# release.net
KiCad netlist of a schematic drawn in EAGLE
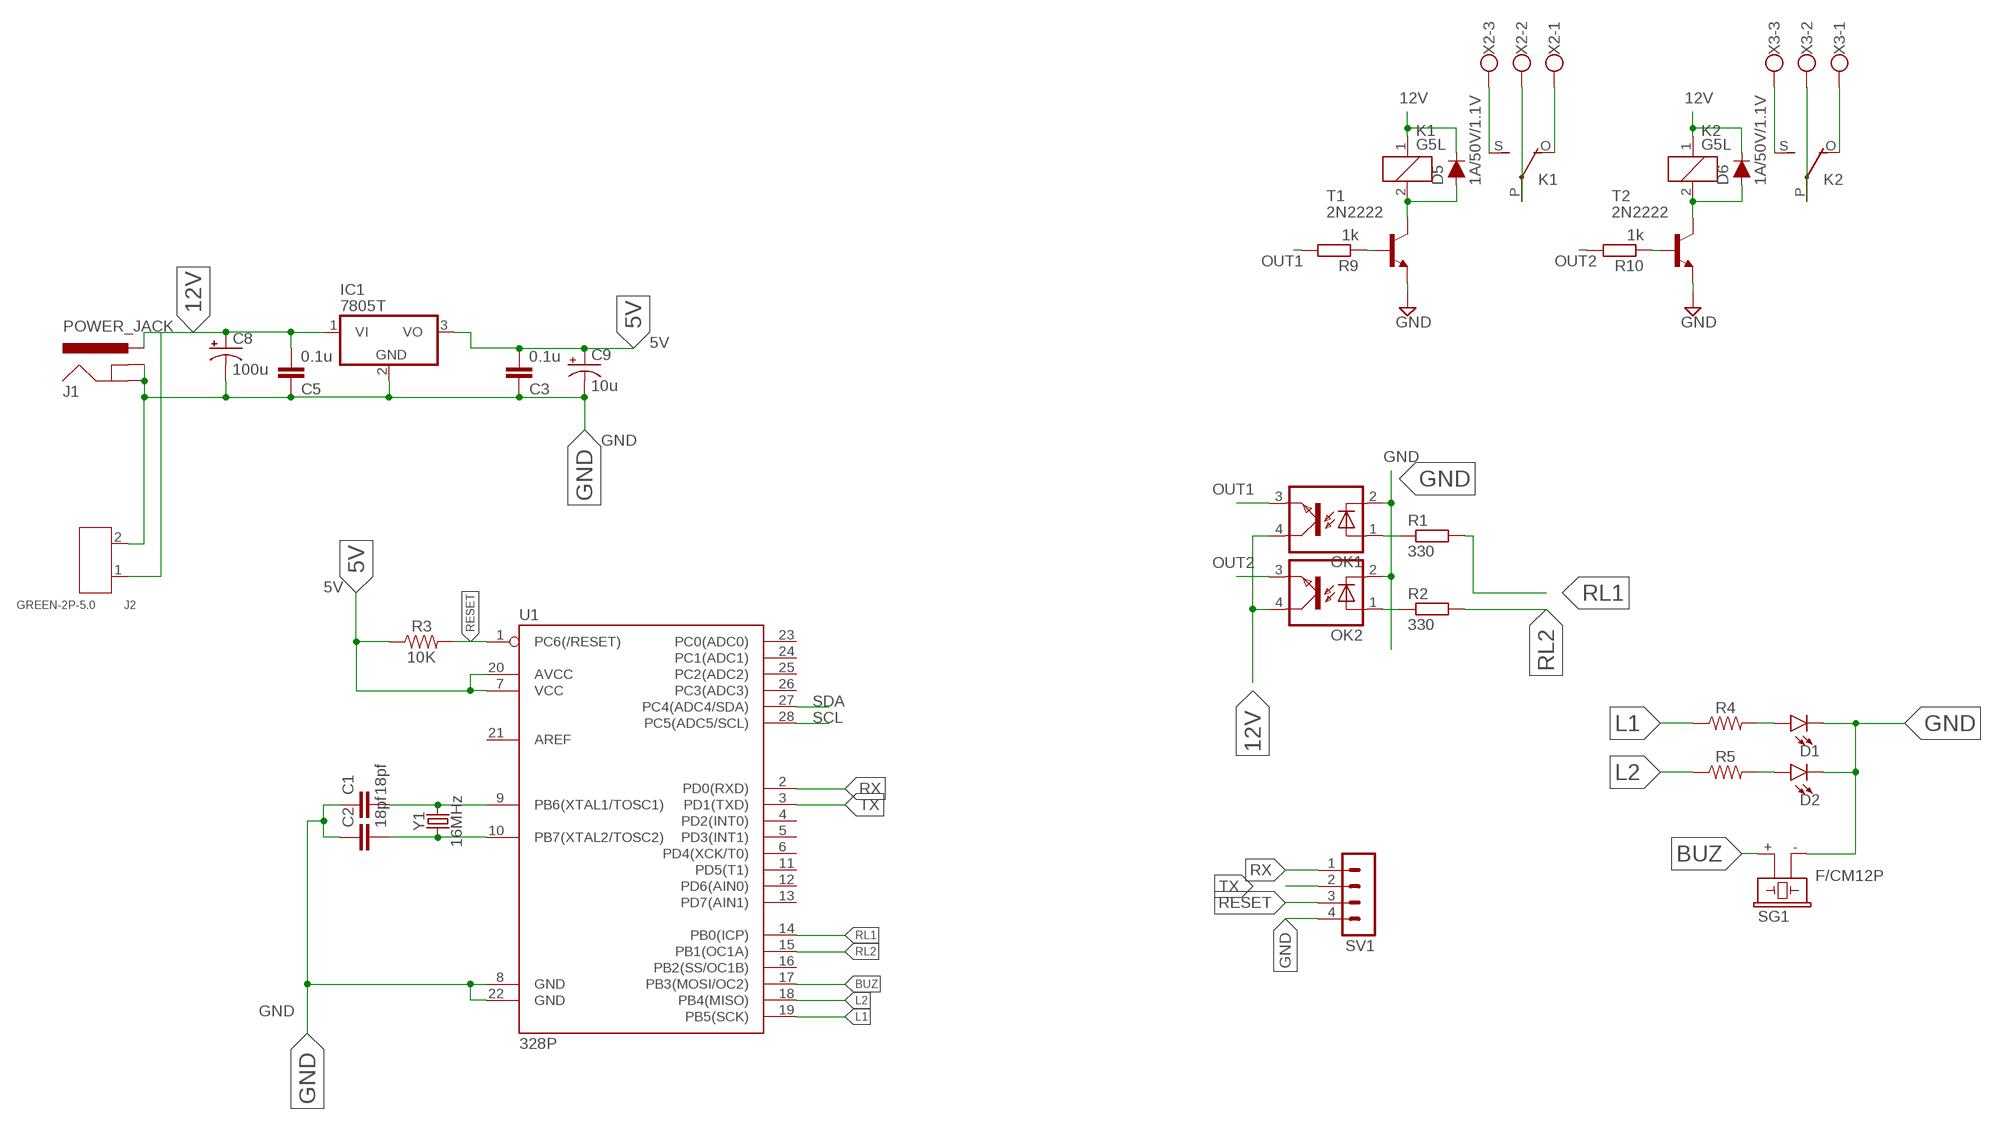
[diagram p0: schematic, sheet 1]

(export (version "E")
  (design (tool "Eeschema 10.0.6"))
  (components
    (comp (ref "C1")
      (value "18pf")
      (footprint "eagle-import:C2.5-3")
      (libsource (lib "eagle-import") (part "C2,5-3"))
    )
    (comp (ref "C2")
      (value "18pf")
      (footprint "eagle-import:C2.5-3")
      (libsource (lib "eagle-import") (part "C2,5-3"))
    )
    (comp (ref "C3")
      (value "0.1u")
      (footprint "eagle-import:C2.5-3")
      (libsource (lib "eagle-import") (part "C2,5-3"))
    )
    (comp (ref "C5")
      (value "0.1u")
      (footprint "eagle-import:C2.5-3")
      (libsource (lib "eagle-import") (part "C2,5-3"))
    )
    (comp (ref "C8")
      (value "100u")
      (footprint "eagle-import:E2,5-7")
      (libsource (lib "eagle-import") (part "CPOL-USE2.5-7"))
    )
    (comp (ref "C9")
      (value "10u")
      (footprint "eagle-import:E2,5-5")
      (libsource (lib "eagle-import") (part "CPOL-USE2.5-5"))
    )
    (comp (ref "D1")
      (value "LED5MM")
      (footprint "eagle-import:LED_5MM")
      (libsource (lib "eagle-import") (part "LED5MM"))
    )
    (comp (ref "D2")
      (value "LED5MM")
      (footprint "eagle-import:LED_5MM")
      (libsource (lib "eagle-import") (part "LED5MM"))
    )
    (comp (ref "D5")
      (value "1A/50V/1.1V")
      (footprint "eagle-import:DIODE-1N4001")
      (libsource (lib "eagle-import") (part "DIODE-PTH"))
    )
    (comp (ref "D6")
      (value "1A/50V/1.1V")
      (footprint "eagle-import:DIODE-1N4001")
      (libsource (lib "eagle-import") (part "DIODE-PTH"))
    )
    (comp (ref "IC1")
      (value "7805T")
      (footprint "eagle-import:TO220H")
      (libsource (lib "eagle-import") (part "78T05"))
    )
    (comp (ref "J1")
      (value "POWER_JACK")
      (footprint "eagle-import:POWER_JACK_PTH")
      (libsource (lib "eagle-import") (part "POWER_JACK"))
    )
    (comp (ref "J2")
      (value "GREEN-2P-5.0")
      (footprint "eagle-import:H2-5.0-10.5X8.0MM")
      (libsource (lib "eagle-import") (part "SCREW-TERMINAL-GREEN(2P-5.0)"))
    )
    (comp (ref "K1")
      (value "G5L")
      (footprint "eagle-import:G5LE")
      (libsource (lib "eagle-import") (part "G5L"))
    )
    (comp (ref "K2")
      (value "G5L")
      (footprint "eagle-import:G5LE")
      (libsource (lib "eagle-import") (part "G5L"))
    )
    (comp (ref "OK1")
      (value "LTV816")
      (footprint "eagle-import:DIL04")
      (libsource (lib "eagle-import") (part "LTV816"))
    )
    (comp (ref "OK2")
      (value "LTV816")
      (footprint "eagle-import:DIL04")
      (libsource (lib "eagle-import") (part "LTV816"))
    )
    (comp (ref "R1")
      (value "330")
      (footprint "eagle-import:0207_7")
      (libsource (lib "eagle-import") (part "R-EU_0207/7"))
    )
    (comp (ref "R2")
      (value "330")
      (footprint "eagle-import:0207_7")
      (libsource (lib "eagle-import") (part "R-EU_0207/7"))
    )
    (comp (ref "R3")
      (value "10K")
      (footprint "eagle-import:AXIAL-0.3")
      (libsource (lib "eagle-import") (part "1KOHM-HORIZ-1/4W-5%"))
    )
    (comp (ref "R4")
      (value "RESISTORAXIAL-0.3")
      (footprint "eagle-import:AXIAL-0.3")
      (libsource (lib "eagle-import") (part "RESISTORAXIAL-0.3"))
    )
    (comp (ref "R5")
      (value "RESISTORAXIAL-0.3")
      (footprint "eagle-import:AXIAL-0.3")
      (libsource (lib "eagle-import") (part "RESISTORAXIAL-0.3"))
    )
    (comp (ref "R9")
      (value "1k")
      (footprint "eagle-import:0207_7")
      (libsource (lib "eagle-import") (part "resistor_348_R-EU_0207/7"))
    )
    (comp (ref "R10")
      (value "1k")
      (footprint "eagle-import:0207_7")
      (libsource (lib "eagle-import") (part "resistor_348_R-EU_0207/7"))
    )
    (comp (ref "SG1")
      (value "F/CM12P")
      (footprint "eagle-import:F_CM12P")
      (libsource (lib "eagle-import") (part "F/CM12P"))
    )
    (comp (ref "SV1")
      (value "MA04-1")
      (footprint "eagle-import:MA04-1")
      (libsource (lib "eagle-import") (part "MA04-1"))
    )
    (comp (ref "T1")
      (value "2N2222")
      (footprint "eagle-import:TO92-EBC-OVAL")
      (libsource (lib "eagle-import") (part "2N2222"))
    )
    (comp (ref "T2")
      (value "2N2222")
      (footprint "eagle-import:TO92-EBC-OVAL")
      (libsource (lib "eagle-import") (part "2N2222"))
    )
    (comp (ref "U1")
      (value "328P")
      (footprint "eagle-import:DIP28")
      (libsource (lib "eagle-import") (part "ATMEGA328P_PDIP"))
    )
    (comp (ref "X2")
      (value "W237-103")
      (footprint "eagle-import:W237-103")
      (fields (field (name "MPN") "237-103"))
      (libsource (lib "eagle-import") (part "W237-103"))
    )
    (comp (ref "X3")
      (value "W237-103")
      (footprint "eagle-import:W237-103")
      (fields (field (name "MPN") "237-103"))
      (libsource (lib "eagle-import") (part "W237-103"))
    )
    (comp (ref "Y1")
      (value "16MHz")
      (footprint "eagle-import:HC49US")
      (libsource (lib "eagle-import") (part "CRYSTAL-16MHZPTH-HC49US"))
    )
  )
  (nets
    (net (code "1") (name "/OUT1") (class "Default")
      (node (ref "OK1") (pin "3") (pinfunction "EMIT_3") (pintype "passive"))
      (node (ref "R9") (pin "2") (pinfunction "2_2") (pintype "passive"))
    )
    (net (code "2") (name "/OUT2") (class "Default")
      (node (ref "OK2") (pin "3") (pinfunction "EMIT_3") (pintype "passive"))
      (node (ref "R10") (pin "2") (pinfunction "2_2") (pintype "passive"))
    )
    (net (code "3") (name "/SCL") (class "Default")
      (node (ref "U1") (pin "28") (pinfunction "PC5(ADC5/SCL)_28") (pintype "bidirectional"))
    )
    (net (code "4") (name "/SDA") (class "Default")
      (node (ref "U1") (pin "27") (pinfunction "PC4(ADC4/SDA)_27") (pintype "bidirectional"))
    )
    (net (code "5") (name "5V") (class "Default")
      (node (ref "C3") (pin "2") (pinfunction "2_2") (pintype "passive"))
      (node (ref "C9") (pin "+") (pinfunction "+_+") (pintype "passive"))
      (node (ref "IC1") (pin "3") (pinfunction "VO_3") (pintype "passive"))
      (node (ref "R3") (pin "P$1") (pinfunction "1_P$1") (pintype "passive"))
      (node (ref "U1") (pin "20") (pinfunction "AVCC_20") (pintype "bidirectional"))
      (node (ref "U1") (pin "7") (pinfunction "VCC_7") (pintype "bidirectional"))
    )
    (net (code "6") (name "12V") (class "Default")
      (node (ref "C5") (pin "2") (pinfunction "2_2") (pintype "passive"))
      (node (ref "C8") (pin "+") (pinfunction "+_+") (pintype "passive"))
      (node (ref "D5") (pin "C") (pinfunction "C_C") (pintype "passive"))
      (node (ref "D6") (pin "C") (pinfunction "C_C") (pintype "passive"))
      (node (ref "IC1") (pin "1") (pinfunction "VI_1") (pintype "input"))
      (node (ref "J1") (pin "PWR") (pinfunction "PWR_PWR") (pintype "bidirectional"))
      (node (ref "J2") (pin "1") (pinfunction "1_1") (pintype "bidirectional"))
      (node (ref "K1") (pin "1") (pinfunction "1_1") (pintype "passive"))
      (node (ref "K2") (pin "1") (pinfunction "1_1") (pintype "passive"))
      (node (ref "OK1") (pin "4") (pinfunction "COL_4") (pintype "passive"))
      (node (ref "OK2") (pin "4") (pinfunction "COL_4") (pintype "passive"))
    )
    (net (code "7") (name "BUZ") (class "Default")
      (node (ref "SG1") (pin "+") (pinfunction "1_+") (pintype "passive"))
      (node (ref "U1") (pin "17") (pinfunction "PB3(MOSI/OC2)_17") (pintype "bidirectional"))
    )
    (net (code "8") (name "GND") (class "Default")
      (node (ref "C1") (pin "1") (pinfunction "1_1") (pintype "passive"))
      (node (ref "C2") (pin "1") (pinfunction "1_1") (pintype "passive"))
      (node (ref "C3") (pin "1") (pinfunction "1_1") (pintype "passive"))
      (node (ref "C5") (pin "1") (pinfunction "1_1") (pintype "passive"))
      (node (ref "C8") (pin "-") (pinfunction "-_-") (pintype "passive"))
      (node (ref "C9") (pin "-") (pinfunction "-_-") (pintype "passive"))
      (node (ref "D1") (pin "K") (pinfunction "C_K") (pintype "passive"))
      (node (ref "D2") (pin "K") (pinfunction "C_K") (pintype "passive"))
      (node (ref "IC1") (pin "2") (pinfunction "GND_2") (pintype "passive"))
      (node (ref "J1") (pin "GND") (pinfunction "GND_GND") (pintype "bidirectional"))
      (node (ref "J1") (pin "GNDBREAK") (pinfunction "GNDBREAK_GNDBREAK") (pintype "bidirectional"))
      (node (ref "J2") (pin "2") (pinfunction "2_2") (pintype "bidirectional"))
      (node (ref "OK1") (pin "2") (pinfunction "C_2") (pintype "passive"))
      (node (ref "OK2") (pin "2") (pinfunction "C_2") (pintype "passive"))
      (node (ref "SG1") (pin "-") (pinfunction "2_-") (pintype "passive"))
      (node (ref "SV1") (pin "4") (pinfunction "4_4") (pintype "passive"))
      (node (ref "T1") (pin "E") (pinfunction "E_E") (pintype "passive"))
      (node (ref "T2") (pin "E") (pinfunction "E_E") (pintype "passive"))
      (node (ref "U1") (pin "22") (pinfunction "GND_22") (pintype "bidirectional"))
      (node (ref "U1") (pin "8") (pinfunction "GND_8") (pintype "bidirectional"))
    )
    (net (code "9") (name "L1") (class "Default")
      (node (ref "R4") (pin "P$1") (pinfunction "1_P$1") (pintype "passive"))
      (node (ref "U1") (pin "19") (pinfunction "PB5(SCK)_19") (pintype "bidirectional"))
    )
    (net (code "10") (name "L2") (class "Default")
      (node (ref "R5") (pin "P$1") (pinfunction "1_P$1") (pintype "passive"))
      (node (ref "U1") (pin "18") (pinfunction "PB4(MISO)_18") (pintype "bidirectional"))
    )
    (net (code "11") (name "Net-(D5-PadA)") (class "Default")
      (node (ref "D5") (pin "A") (pinfunction "A_A") (pintype "passive"))
      (node (ref "K1") (pin "2") (pinfunction "2_2") (pintype "passive"))
      (node (ref "T1") (pin "C") (pinfunction "C_C") (pintype "passive"))
    )
    (net (code "12") (name "Net-(D6-PadA)") (class "Default")
      (node (ref "D6") (pin "A") (pinfunction "A_A") (pintype "passive"))
      (node (ref "K2") (pin "2") (pinfunction "2_2") (pintype "passive"))
      (node (ref "T2") (pin "C") (pinfunction "C_C") (pintype "passive"))
    )
    (net (code "13") (name "Net-(OK1-A)") (class "Default")
      (node (ref "OK1") (pin "1") (pinfunction "A_1") (pintype "passive"))
      (node (ref "R1") (pin "1") (pinfunction "1_1") (pintype "passive"))
    )
    (net (code "14") (name "Net-(OK2-A)") (class "Default")
      (node (ref "OK2") (pin "1") (pinfunction "A_1") (pintype "passive"))
      (node (ref "R2") (pin "1") (pinfunction "1_1") (pintype "passive"))
    )
    (net (code "15") (name "Net-(R4-2)") (class "Default")
      (node (ref "D1") (pin "A") (pinfunction "A_A") (pintype "passive"))
      (node (ref "R4") (pin "P$2") (pinfunction "2_P$2") (pintype "passive"))
    )
    (net (code "16") (name "Net-(R5-2)") (class "Default")
      (node (ref "D2") (pin "A") (pinfunction "A_A") (pintype "passive"))
      (node (ref "R5") (pin "P$2") (pinfunction "2_P$2") (pintype "passive"))
    )
    (net (code "17") (name "Net-(R9-Pad1)") (class "Default")
      (node (ref "R9") (pin "1") (pinfunction "1_1") (pintype "passive"))
      (node (ref "T1") (pin "B") (pinfunction "B_B") (pintype "passive"))
    )
    (net (code "18") (name "Net-(R10-Pad1)") (class "Default")
      (node (ref "R10") (pin "1") (pinfunction "1_1") (pintype "passive"))
      (node (ref "T2") (pin "B") (pinfunction "B_B") (pintype "passive"))
    )
    (net (code "19") (name "Net-(U1-PB6(XTAL1{slash}TOSC1))") (class "Default")
      (node (ref "C1") (pin "2") (pinfunction "2_2") (pintype "passive"))
      (node (ref "U1") (pin "9") (pinfunction "PB6(XTAL1/TOSC1)_9") (pintype "bidirectional"))
      (node (ref "Y1") (pin "2") (pinfunction "2_2") (pintype "passive"))
    )
    (net (code "20") (name "Net-(U1-PB7(XTAL2{slash}TOSC2))") (class "Default")
      (node (ref "C2") (pin "2") (pinfunction "2_2") (pintype "passive"))
      (node (ref "U1") (pin "10") (pinfunction "PB7(XTAL2/TOSC2)_10") (pintype "bidirectional"))
      (node (ref "Y1") (pin "1") (pinfunction "1_1") (pintype "passive"))
    )
    (net (code "21") (name "Net-(X2A-KL)") (class "Default")
      (node (ref "K1") (pin "O") (pinfunction "O_O") (pintype "passive"))
      (node (ref "X2") (pin "1") (pinfunction "KL_1") (pintype "passive"))
    )
    (net (code "22") (name "Net-(X2B-KL)") (class "Default")
      (node (ref "K1") (pin "P") (pinfunction "P_P") (pintype "passive"))
      (node (ref "X2") (pin "2") (pinfunction "KL_2") (pintype "passive"))
    )
    (net (code "23") (name "Net-(X2C-KL)") (class "Default")
      (node (ref "K1") (pin "S") (pinfunction "S_S") (pintype "passive"))
      (node (ref "X2") (pin "3") (pinfunction "KL_3") (pintype "passive"))
    )
    (net (code "24") (name "Net-(X3A-KL)") (class "Default")
      (node (ref "K2") (pin "O") (pinfunction "O_O") (pintype "passive"))
      (node (ref "X3") (pin "1") (pinfunction "KL_1") (pintype "passive"))
    )
    (net (code "25") (name "Net-(X3B-KL)") (class "Default")
      (node (ref "K2") (pin "P") (pinfunction "P_P") (pintype "passive"))
      (node (ref "X3") (pin "2") (pinfunction "KL_2") (pintype "passive"))
    )
    (net (code "26") (name "Net-(X3C-KL)") (class "Default")
      (node (ref "K2") (pin "S") (pinfunction "S_S") (pintype "passive"))
      (node (ref "X3") (pin "3") (pinfunction "KL_3") (pintype "passive"))
    )
    (net (code "27") (name "RESET") (class "Default")
      (node (ref "R3") (pin "P$2") (pinfunction "2_P$2") (pintype "passive"))
      (node (ref "SV1") (pin "3") (pinfunction "3_3") (pintype "passive"))
      (node (ref "U1") (pin "1") (pinfunction "PC6(/RESET)_1") (pintype "bidirectional"))
    )
    (net (code "28") (name "RL1") (class "Default")
      (node (ref "R1") (pin "2") (pinfunction "2_2") (pintype "passive"))
      (node (ref "U1") (pin "14") (pinfunction "PB0(ICP)_14") (pintype "bidirectional"))
    )
    (net (code "29") (name "RL2") (class "Default")
      (node (ref "R2") (pin "2") (pinfunction "2_2") (pintype "passive"))
      (node (ref "U1") (pin "15") (pinfunction "PB1(OC1A)_15") (pintype "bidirectional"))
    )
    (net (code "30") (name "RX") (class "Default")
      (node (ref "SV1") (pin "1") (pinfunction "1_1") (pintype "passive"))
      (node (ref "U1") (pin "2") (pinfunction "PD0(RXD)_2") (pintype "bidirectional"))
    )
    (net (code "31") (name "TX") (class "Default")
      (node (ref "SV1") (pin "2") (pinfunction "2_2") (pintype "passive"))
      (node (ref "U1") (pin "3") (pinfunction "PD1(TXD)_3") (pintype "bidirectional"))
    )
    (net (code "32") (name "unconnected-(U1-AREF-Pad21)") (class "Default")
      (node (ref "U1") (pin "21") (pinfunction "AREF_21") (pintype "bidirectional"))
    )
    (net (code "33") (name "unconnected-(U1-PB2(SS{slash}OC1B)-Pad16)") (class "Default")
      (node (ref "U1") (pin "16") (pinfunction "PB2(SS/OC1B)_16") (pintype "bidirectional"))
    )
    (net (code "34") (name "unconnected-(U1-PC0(ADC0)-Pad23)") (class "Default")
      (node (ref "U1") (pin "23") (pinfunction "PC0(ADC0)_23") (pintype "bidirectional"))
    )
    (net (code "35") (name "unconnected-(U1-PC1(ADC1)-Pad24)") (class "Default")
      (node (ref "U1") (pin "24") (pinfunction "PC1(ADC1)_24") (pintype "bidirectional"))
    )
    (net (code "36") (name "unconnected-(U1-PC2(ADC2)-Pad25)") (class "Default")
      (node (ref "U1") (pin "25") (pinfunction "PC2(ADC2)_25") (pintype "bidirectional"))
    )
    (net (code "37") (name "unconnected-(U1-PC3(ADC3)-Pad26)") (class "Default")
      (node (ref "U1") (pin "26") (pinfunction "PC3(ADC3)_26") (pintype "bidirectional"))
    )
    (net (code "38") (name "unconnected-(U1-PD2(INT0)-Pad4)") (class "Default")
      (node (ref "U1") (pin "4") (pinfunction "PD2(INT0)_4") (pintype "bidirectional"))
    )
    (net (code "39") (name "unconnected-(U1-PD3(INT1)-Pad5)") (class "Default")
      (node (ref "U1") (pin "5") (pinfunction "PD3(INT1)_5") (pintype "bidirectional"))
    )
    (net (code "40") (name "unconnected-(U1-PD4(XCK{slash}T0)-Pad6)") (class "Default")
      (node (ref "U1") (pin "6") (pinfunction "PD4(XCK/T0)_6") (pintype "bidirectional"))
    )
    (net (code "41") (name "unconnected-(U1-PD5(T1)-Pad11)") (class "Default")
      (node (ref "U1") (pin "11") (pinfunction "PD5(T1)_11") (pintype "bidirectional"))
    )
    (net (code "42") (name "unconnected-(U1-PD6(AIN0)-Pad12)") (class "Default")
      (node (ref "U1") (pin "12") (pinfunction "PD6(AIN0)_12") (pintype "bidirectional"))
    )
    (net (code "43") (name "unconnected-(U1-PD7(AIN1)-Pad13)") (class "Default")
      (node (ref "U1") (pin "13") (pinfunction "PD7(AIN1)_13") (pintype "bidirectional"))
    )
  )
)
